# SMAC-2530.net
KiCad netlist of a schematic drawn in EAGLE
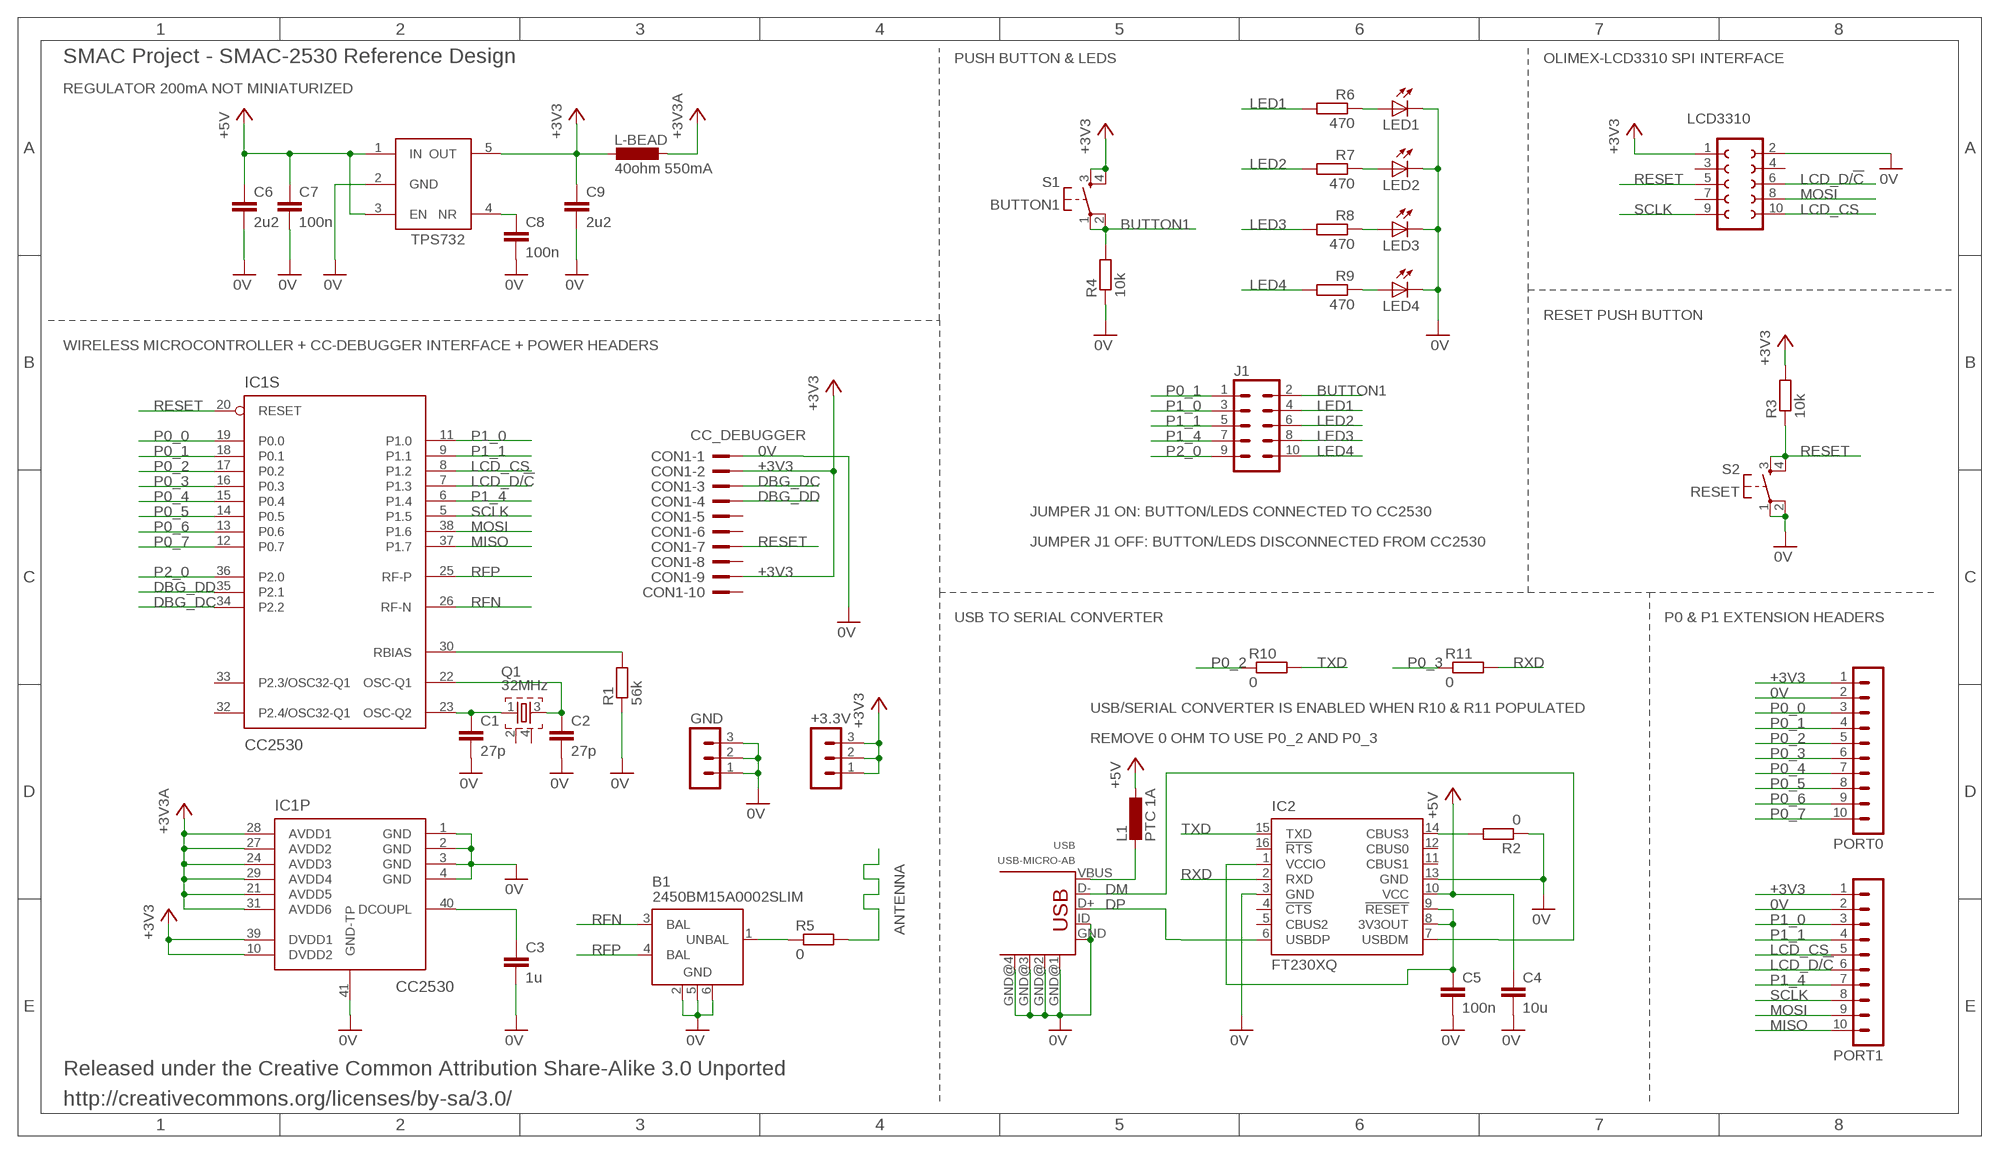
[diagram p0: schematic, sheet 1]

(export (version "E")
  (design (tool "Eeschema 10.0.6"))
  (components
    (comp (ref "+3.3V")
      (value "MA03-1")
      (footprint "eagle-import:MA03-1")
      (libsource (lib "eagle-import") (part "MA03-1"))
    )
    (comp (ref "B1")
      (value "2450BM15A0002SLIM")
      (footprint "eagle-import:2450BM15A0002-SLIM")
      (libsource (lib "eagle-import") (part "2450BM15A0002SLIM"))
    )
    (comp (ref "C1")
      (value "27p")
      (footprint "eagle-import:C0603K")
      (libsource (lib "eagle-import") (part "C-EUC0603K"))
    )
    (comp (ref "C2")
      (value "27p")
      (footprint "eagle-import:C0603K")
      (libsource (lib "eagle-import") (part "C-EUC0603K"))
    )
    (comp (ref "C3")
      (value "1u")
      (footprint "eagle-import:C0603K")
      (libsource (lib "eagle-import") (part "C-EUC0603K"))
    )
    (comp (ref "C4")
      (value "10u")
      (footprint "eagle-import:C0603K")
      (libsource (lib "eagle-import") (part "C-EUC0603K"))
    )
    (comp (ref "C5")
      (value "100n")
      (footprint "eagle-import:C0603K")
      (libsource (lib "eagle-import") (part "C-EUC0603K"))
    )
    (comp (ref "C6")
      (value "2u2")
      (footprint "eagle-import:C0603K")
      (libsource (lib "eagle-import") (part "C-EUC0603K"))
    )
    (comp (ref "C7")
      (value "100n")
      (footprint "eagle-import:C0603K")
      (libsource (lib "eagle-import") (part "C-EUC0603K"))
    )
    (comp (ref "C8")
      (value "100n")
      (footprint "eagle-import:C0603K")
      (libsource (lib "eagle-import") (part "C-EUC0603K"))
    )
    (comp (ref "C9")
      (value "2u2")
      (footprint "eagle-import:C0603K")
      (libsource (lib "eagle-import") (part "C-EUC0603K"))
    )
    (comp (ref "CON1")
      (value "CC_DEBUGGER")
      (footprint "eagle-import:PAK100_2500-10")
      (fields (field (name "MF") "3M") (field (name "MPN") "2510-6002UB"))
      (libsource (lib "eagle-import") (part "2510-"))
    )
    (comp (ref "GND")
      (value "MA03-1")
      (footprint "eagle-import:MA03-1")
      (libsource (lib "eagle-import") (part "MA03-1"))
    )
    (comp (ref "IC1")
      (value "CC2530")
      (footprint "eagle-import:QFN50P600X600X100-41N")
      (libsource (lib "eagle-import") (part "CC2530"))
    )
    (comp (ref "IC2")
      (value "FT230XQ")
      (footprint "eagle-import:QFN16")
      (libsource (lib "eagle-import") (part "FT230XQ"))
    )
    (comp (ref "IC3")
      (value "TPS732XX")
      (footprint "eagle-import:SOT23")
      (libsource (lib "eagle-import") (part "TPS732XX"))
    )
    (comp (ref "J1")
      (value "MA05-2")
      (footprint "eagle-import:MA05-2")
      (libsource (lib "eagle-import") (part "MA05-2"))
    )
    (comp (ref "L-BEAD")
      (value "40ohm 550mA")
      (footprint "eagle-import:L0603K")
      (libsource (lib "eagle-import") (part "L-EUL0603K"))
    )
    (comp (ref "L1")
      (value "PTC 1A")
      (footprint "eagle-import:L0603K")
      (libsource (lib "eagle-import") (part "L-EUL0603K"))
    )
    (comp (ref "LCD3310")
      (value "FE05-2")
      (footprint "eagle-import:FE05-2")
      (libsource (lib "eagle-import") (part "FE05-2"))
    )
    (comp (ref "LED1")
      (value "LEDCHIP-LED0805")
      (footprint "eagle-import:CHIP-LED0805")
      (libsource (lib "eagle-import") (part "LEDCHIP-LED0805"))
    )
    (comp (ref "LED2")
      (value "LEDCHIP-LED0805")
      (footprint "eagle-import:CHIP-LED0805")
      (libsource (lib "eagle-import") (part "LEDCHIP-LED0805"))
    )
    (comp (ref "LED3")
      (value "LEDCHIP-LED0805")
      (footprint "eagle-import:CHIP-LED0805")
      (libsource (lib "eagle-import") (part "LEDCHIP-LED0805"))
    )
    (comp (ref "LED4")
      (value "LEDCHIP-LED0805")
      (footprint "eagle-import:CHIP-LED0805")
      (libsource (lib "eagle-import") (part "LEDCHIP-LED0805"))
    )
    (comp (ref "PORT0")
      (value "MA10-1")
      (footprint "eagle-import:MA10-1")
      (libsource (lib "eagle-import") (part "MA10-1"))
    )
    (comp (ref "PORT1")
      (value "MA10-1")
      (footprint "eagle-import:MA10-1")
      (libsource (lib "eagle-import") (part "MA10-1"))
    )
    (comp (ref "Q1")
      (value "32MHz")
      (footprint "eagle-import:FA-128")
      (libsource (lib "eagle-import") (part "FA-128"))
    )
    (comp (ref "R1")
      (value "56k")
      (footprint "eagle-import:R0603K")
      (libsource (lib "eagle-import") (part "R-EU_R0603K"))
    )
    (comp (ref "R2")
      (value "0")
      (footprint "eagle-import:R0603K")
      (libsource (lib "eagle-import") (part "R-EU_R0603K"))
    )
    (comp (ref "R3")
      (value "10k")
      (footprint "eagle-import:R0603K")
      (libsource (lib "eagle-import") (part "R-EU_R0603K"))
    )
    (comp (ref "R4")
      (value "10k")
      (footprint "eagle-import:R0603K")
      (libsource (lib "eagle-import") (part "R-EU_R0603K"))
    )
    (comp (ref "R5")
      (value "0")
      (footprint "eagle-import:R0603K")
      (libsource (lib "eagle-import") (part "R-EU_R0603K"))
    )
    (comp (ref "R6")
      (value "470")
      (footprint "eagle-import:R0603K")
      (libsource (lib "eagle-import") (part "R-EU_R0603K"))
    )
    (comp (ref "R7")
      (value "470")
      (footprint "eagle-import:R0603K")
      (libsource (lib "eagle-import") (part "R-EU_R0603K"))
    )
    (comp (ref "R8")
      (value "470")
      (footprint "eagle-import:R0603K")
      (libsource (lib "eagle-import") (part "R-EU_R0603K"))
    )
    (comp (ref "R9")
      (value "470")
      (footprint "eagle-import:R0603K")
      (libsource (lib "eagle-import") (part "R-EU_R0603K"))
    )
    (comp (ref "R10")
      (value "0")
      (footprint "eagle-import:R0603K")
      (libsource (lib "eagle-import") (part "R-EU_R0603K"))
    )
    (comp (ref "R11")
      (value "0")
      (footprint "eagle-import:R0603K")
      (libsource (lib "eagle-import") (part "R-EU_R0603K"))
    )
    (comp (ref "S1")
      (value "BUTTON1")
      (footprint "eagle-import:ALCOSWITCH-SMD")
      (libsource (lib "eagle-import") (part "ALCOSWITCH-SMD"))
    )
    (comp (ref "S2")
      (value "RESET")
      (footprint "eagle-import:ALCOSWITCH-SMD")
      (libsource (lib "eagle-import") (part "ALCOSWITCH-SMD"))
    )
    (comp (ref "USB")
      (value "USB-MICRO-AB")
      (footprint "eagle-import:USB-UAB-S1")
      (libsource (lib "eagle-import") (part "USB-OTG_SHIELD"))
    )
  )
  (nets
    (net (code "1") (name "+3V3") (class "Default")
      (node (ref "+3.3V") (pin "1") (pinfunction "1_1") (pintype "passive"))
      (node (ref "+3.3V") (pin "2") (pinfunction "2_2") (pintype "passive"))
      (node (ref "+3.3V") (pin "3") (pinfunction "3_3") (pintype "passive"))
      (node (ref "C9") (pin "1") (pinfunction "1_1") (pintype "passive"))
      (node (ref "CON1") (pin "2") (pinfunction "KL_2") (pintype "passive"))
      (node (ref "CON1") (pin "9") (pinfunction "KL_9") (pintype "passive"))
      (node (ref "IC1") (pin "10") (pinfunction "DVDD2_10") (pintype "power_in"))
      (node (ref "IC1") (pin "39") (pinfunction "DVDD1_39") (pintype "power_in"))
      (node (ref "IC3") (pin "5") (pinfunction "OUT_5") (pintype "bidirectional"))
      (node (ref "L-BEAD") (pin "1") (pinfunction "1_1") (pintype "passive"))
      (node (ref "LCD3310") (pin "1") (pinfunction "1_1") (pintype "passive"))
      (node (ref "PORT0") (pin "1") (pinfunction "1_1") (pintype "passive"))
      (node (ref "PORT1") (pin "1") (pinfunction "1_1") (pintype "passive"))
      (node (ref "R3") (pin "2") (pinfunction "2_2") (pintype "passive"))
      (node (ref "S1") (pin "3") (pinfunction "S_3") (pintype "passive"))
      (node (ref "S1") (pin "4") (pinfunction "S1_4") (pintype "passive"))
    )
    (net (code "2") (name "+3V3A") (class "Default")
      (node (ref "IC1") (pin "21") (pinfunction "AVDD5_21") (pintype "power_in"))
      (node (ref "IC1") (pin "24") (pinfunction "AVDD3_24") (pintype "power_in"))
      (node (ref "IC1") (pin "27") (pinfunction "AVDD2_27") (pintype "power_in"))
      (node (ref "IC1") (pin "28") (pinfunction "AVDD1_28") (pintype "power_in"))
      (node (ref "IC1") (pin "29") (pinfunction "AVDD4_29") (pintype "power_in"))
      (node (ref "IC1") (pin "31") (pinfunction "AVDD6_31") (pintype "power_in"))
      (node (ref "L-BEAD") (pin "2") (pinfunction "2_2") (pintype "passive"))
    )
    (net (code "3") (name "+5V") (class "Default")
      (node (ref "C4") (pin "1") (pinfunction "1_1") (pintype "passive"))
      (node (ref "C6") (pin "1") (pinfunction "1_1") (pintype "passive"))
      (node (ref "C7") (pin "1") (pinfunction "1_1") (pintype "passive"))
      (node (ref "IC2") (pin "10") (pinfunction "VCC_10") (pintype "power_in"))
      (node (ref "IC3") (pin "1") (pinfunction "IN_1") (pintype "bidirectional"))
      (node (ref "IC3") (pin "3") (pinfunction "EN_3") (pintype "bidirectional"))
      (node (ref "L1") (pin "1") (pinfunction "1_1") (pintype "passive"))
    )
    (net (code "4") (name "/BUTTON1") (class "Default")
      (node (ref "J1") (pin "2") (pinfunction "2_2") (pintype "passive"))
      (node (ref "R4") (pin "2") (pinfunction "2_2") (pintype "passive"))
      (node (ref "S1") (pin "1") (pinfunction "P_1") (pintype "passive"))
      (node (ref "S1") (pin "2") (pinfunction "P1_2") (pintype "passive"))
    )
    (net (code "5") (name "/DBG_DC") (class "Default")
      (node (ref "CON1") (pin "3") (pinfunction "KL_3") (pintype "passive"))
      (node (ref "IC1") (pin "34") (pinfunction "P2.2_34") (pintype "bidirectional"))
    )
    (net (code "6") (name "/DBG_DD") (class "Default")
      (node (ref "CON1") (pin "4") (pinfunction "KL_4") (pintype "passive"))
      (node (ref "IC1") (pin "35") (pinfunction "P2.1_35") (pintype "bidirectional"))
    )
    (net (code "7") (name "/DM") (class "Default")
      (node (ref "IC2") (pin "7") (pinfunction "USBDM_7") (pintype "input"))
      (node (ref "USB") (pin "D-") (pinfunction "D-_D-") (pintype "bidirectional"))
    )
    (net (code "8") (name "/DP") (class "Default")
      (node (ref "IC2") (pin "6") (pinfunction "USBDP_6") (pintype "input"))
      (node (ref "USB") (pin "D+") (pinfunction "D+_D+") (pintype "bidirectional"))
    )
    (net (code "9") (name "/LCD_CS") (class "Default")
      (node (ref "IC1") (pin "8") (pinfunction "P1.2_8") (pintype "bidirectional"))
      (node (ref "LCD3310") (pin "10") (pinfunction "10_10") (pintype "passive"))
      (node (ref "PORT1") (pin "5") (pinfunction "5_5") (pintype "passive"))
    )
    (net (code "10") (name "/LCD_D{slash}~{C}") (class "Default")
      (node (ref "IC1") (pin "7") (pinfunction "P1.3_7") (pintype "bidirectional"))
      (node (ref "LCD3310") (pin "6") (pinfunction "6_6") (pintype "passive"))
      (node (ref "PORT1") (pin "6") (pinfunction "6_6") (pintype "passive"))
    )
    (net (code "11") (name "/LED1") (class "Default")
      (node (ref "J1") (pin "4") (pinfunction "4_4") (pintype "passive"))
      (node (ref "R6") (pin "2") (pinfunction "2_2") (pintype "passive"))
    )
    (net (code "12") (name "/LED2") (class "Default")
      (node (ref "J1") (pin "6") (pinfunction "6_6") (pintype "passive"))
      (node (ref "R7") (pin "2") (pinfunction "2_2") (pintype "passive"))
    )
    (net (code "13") (name "/LED3") (class "Default")
      (node (ref "J1") (pin "8") (pinfunction "8_8") (pintype "passive"))
      (node (ref "R8") (pin "2") (pinfunction "2_2") (pintype "passive"))
    )
    (net (code "14") (name "/LED4") (class "Default")
      (node (ref "J1") (pin "10") (pinfunction "10_10") (pintype "passive"))
      (node (ref "R9") (pin "2") (pinfunction "2_2") (pintype "passive"))
    )
    (net (code "15") (name "/MISO") (class "Default")
      (node (ref "IC1") (pin "37") (pinfunction "P1.7_37") (pintype "bidirectional"))
      (node (ref "PORT1") (pin "10") (pinfunction "10_10") (pintype "passive"))
    )
    (net (code "16") (name "/MOSI") (class "Default")
      (node (ref "IC1") (pin "38") (pinfunction "P1.6_38") (pintype "bidirectional"))
      (node (ref "LCD3310") (pin "8") (pinfunction "8_8") (pintype "passive"))
      (node (ref "PORT1") (pin "9") (pinfunction "9_9") (pintype "passive"))
    )
    (net (code "17") (name "/P0_0") (class "Default")
      (node (ref "IC1") (pin "19") (pinfunction "P0.0_19") (pintype "bidirectional"))
      (node (ref "PORT0") (pin "3") (pinfunction "3_3") (pintype "passive"))
    )
    (net (code "18") (name "/P0_1") (class "Default")
      (node (ref "IC1") (pin "18") (pinfunction "P0.1_18") (pintype "bidirectional"))
      (node (ref "J1") (pin "1") (pinfunction "1_1") (pintype "passive"))
      (node (ref "PORT0") (pin "4") (pinfunction "4_4") (pintype "passive"))
    )
    (net (code "19") (name "/P0_2") (class "Default")
      (node (ref "IC1") (pin "17") (pinfunction "P0.2_17") (pintype "bidirectional"))
      (node (ref "PORT0") (pin "5") (pinfunction "5_5") (pintype "passive"))
      (node (ref "R10") (pin "1") (pinfunction "1_1") (pintype "passive"))
    )
    (net (code "20") (name "/P0_3") (class "Default")
      (node (ref "IC1") (pin "16") (pinfunction "P0.3_16") (pintype "bidirectional"))
      (node (ref "PORT0") (pin "6") (pinfunction "6_6") (pintype "passive"))
      (node (ref "R11") (pin "1") (pinfunction "1_1") (pintype "passive"))
    )
    (net (code "21") (name "/P0_4") (class "Default")
      (node (ref "IC1") (pin "15") (pinfunction "P0.4_15") (pintype "bidirectional"))
      (node (ref "PORT0") (pin "7") (pinfunction "7_7") (pintype "passive"))
    )
    (net (code "22") (name "/P0_5") (class "Default")
      (node (ref "IC1") (pin "14") (pinfunction "P0.5_14") (pintype "bidirectional"))
      (node (ref "PORT0") (pin "8") (pinfunction "8_8") (pintype "passive"))
    )
    (net (code "23") (name "/P0_6") (class "Default")
      (node (ref "IC1") (pin "13") (pinfunction "P0.6_13") (pintype "bidirectional"))
      (node (ref "PORT0") (pin "9") (pinfunction "9_9") (pintype "passive"))
    )
    (net (code "24") (name "/P0_7") (class "Default")
      (node (ref "IC1") (pin "12") (pinfunction "P0.7_12") (pintype "bidirectional"))
      (node (ref "PORT0") (pin "10") (pinfunction "10_10") (pintype "passive"))
    )
    (net (code "25") (name "/P1_0") (class "Default")
      (node (ref "IC1") (pin "11") (pinfunction "P1.0_11") (pintype "bidirectional"))
      (node (ref "J1") (pin "3") (pinfunction "3_3") (pintype "passive"))
      (node (ref "PORT1") (pin "3") (pinfunction "3_3") (pintype "passive"))
    )
    (net (code "26") (name "/P1_1") (class "Default")
      (node (ref "IC1") (pin "9") (pinfunction "P1.1_9") (pintype "bidirectional"))
      (node (ref "J1") (pin "5") (pinfunction "5_5") (pintype "passive"))
      (node (ref "PORT1") (pin "4") (pinfunction "4_4") (pintype "passive"))
    )
    (net (code "27") (name "/P1_4") (class "Default")
      (node (ref "IC1") (pin "6") (pinfunction "P1.4_6") (pintype "bidirectional"))
      (node (ref "J1") (pin "7") (pinfunction "7_7") (pintype "passive"))
      (node (ref "PORT1") (pin "7") (pinfunction "7_7") (pintype "passive"))
    )
    (net (code "28") (name "/P2_0") (class "Default")
      (node (ref "IC1") (pin "36") (pinfunction "P2.0_36") (pintype "bidirectional"))
      (node (ref "J1") (pin "9") (pinfunction "9_9") (pintype "passive"))
    )
    (net (code "29") (name "/RESET") (class "Default")
      (node (ref "CON1") (pin "7") (pinfunction "KL_7") (pintype "passive"))
      (node (ref "IC1") (pin "20") (pinfunction "RESET_20") (pintype "input"))
      (node (ref "LCD3310") (pin "5") (pinfunction "5_5") (pintype "passive"))
      (node (ref "R3") (pin "1") (pinfunction "1_1") (pintype "passive"))
      (node (ref "S2") (pin "3") (pinfunction "S_3") (pintype "passive"))
      (node (ref "S2") (pin "4") (pinfunction "S1_4") (pintype "passive"))
    )
    (net (code "30") (name "/RFN") (class "Default")
      (node (ref "B1") (pin "3") (pinfunction "BAL_3") (pintype "passive"))
      (node (ref "IC1") (pin "26") (pinfunction "RF-N_26") (pintype "bidirectional"))
    )
    (net (code "31") (name "/RFP") (class "Default")
      (node (ref "B1") (pin "4") (pinfunction "BAL_4") (pintype "passive"))
      (node (ref "IC1") (pin "25") (pinfunction "RF-P_25") (pintype "bidirectional"))
    )
    (net (code "32") (name "/RXD") (class "Default")
      (node (ref "IC2") (pin "2") (pinfunction "RXD_2") (pintype "input"))
      (node (ref "R11") (pin "2") (pinfunction "2_2") (pintype "passive"))
    )
    (net (code "33") (name "/SCLK") (class "Default")
      (node (ref "IC1") (pin "5") (pinfunction "P1.5_5") (pintype "bidirectional"))
      (node (ref "LCD3310") (pin "9") (pinfunction "9_9") (pintype "passive"))
      (node (ref "PORT1") (pin "8") (pinfunction "8_8") (pintype "passive"))
    )
    (net (code "34") (name "/TXD") (class "Default")
      (node (ref "IC2") (pin "15") (pinfunction "TXD_15") (pintype "output"))
      (node (ref "R10") (pin "2") (pinfunction "2_2") (pintype "passive"))
    )
    (net (code "35") (name "0V") (class "Default")
      (node (ref "B1") (pin "2") (pinfunction "GND_2") (pintype "passive"))
      (node (ref "B1") (pin "5") (pinfunction "GND_5") (pintype "passive"))
      (node (ref "B1") (pin "6") (pinfunction "GND_6") (pintype "passive"))
      (node (ref "C1") (pin "2") (pinfunction "2_2") (pintype "passive"))
      (node (ref "C2") (pin "2") (pinfunction "2_2") (pintype "passive"))
      (node (ref "C3") (pin "2") (pinfunction "2_2") (pintype "passive"))
      (node (ref "C4") (pin "2") (pinfunction "2_2") (pintype "passive"))
      (node (ref "C5") (pin "2") (pinfunction "2_2") (pintype "passive"))
      (node (ref "C6") (pin "2") (pinfunction "2_2") (pintype "passive"))
      (node (ref "C7") (pin "2") (pinfunction "2_2") (pintype "passive"))
      (node (ref "C8") (pin "2") (pinfunction "2_2") (pintype "passive"))
      (node (ref "C9") (pin "2") (pinfunction "2_2") (pintype "passive"))
      (node (ref "CON1") (pin "1") (pinfunction "KL_1") (pintype "passive"))
      (node (ref "GND") (pin "1") (pinfunction "1_1") (pintype "passive"))
      (node (ref "GND") (pin "2") (pinfunction "2_2") (pintype "passive"))
      (node (ref "GND") (pin "3") (pinfunction "3_3") (pintype "passive"))
      (node (ref "IC1") (pin "1") (pinfunction "GND_1") (pintype "power_in"))
      (node (ref "IC1") (pin "2") (pinfunction "GND_2") (pintype "power_in"))
      (node (ref "IC1") (pin "3") (pinfunction "GND_3") (pintype "power_in"))
      (node (ref "IC1") (pin "4") (pinfunction "GND_4") (pintype "power_in"))
      (node (ref "IC1") (pin "41") (pinfunction "GND-TP_41") (pintype "power_in"))
      (node (ref "IC2") (pin "13") (pinfunction "GND_13") (pintype "power_in"))
      (node (ref "IC2") (pin "3") (pinfunction "GND_3") (pintype "power_in"))
      (node (ref "IC3") (pin "2") (pinfunction "GND_2") (pintype "bidirectional"))
      (node (ref "LCD3310") (pin "2") (pinfunction "2_2") (pintype "passive"))
      (node (ref "LED1") (pin "C") (pinfunction "C_C") (pintype "passive"))
      (node (ref "LED2") (pin "C") (pinfunction "C_C") (pintype "passive"))
      (node (ref "LED3") (pin "C") (pinfunction "C_C") (pintype "passive"))
      (node (ref "LED4") (pin "C") (pinfunction "C_C") (pintype "passive"))
      (node (ref "PORT0") (pin "2") (pinfunction "2_2") (pintype "passive"))
      (node (ref "PORT1") (pin "2") (pinfunction "2_2") (pintype "passive"))
      (node (ref "R1") (pin "1") (pinfunction "1_1") (pintype "passive"))
      (node (ref "R2") (pin "1") (pinfunction "1_1") (pintype "passive"))
      (node (ref "R4") (pin "1") (pinfunction "1_1") (pintype "passive"))
      (node (ref "R5") (pin "2") (pinfunction "2_2") (pintype "passive"))
      (node (ref "S2") (pin "1") (pinfunction "P_1") (pintype "passive"))
      (node (ref "S2") (pin "2") (pinfunction "P1_2") (pintype "passive"))
      (node (ref "USB") (pin "GND") (pinfunction "GND_GND") (pintype "power_in"))
      (node (ref "USB") (pin "GND@1") (pinfunction "GND_GND@1") (pintype "power_in"))
      (node (ref "USB") (pin "GND@2") (pinfunction "GND_GND@2") (pintype "power_in"))
      (node (ref "USB") (pin "GND@3") (pinfunction "GND_GND@3") (pintype "power_in"))
      (node (ref "USB") (pin "GND@4") (pinfunction "GND_GND@4") (pintype "power_in"))
      (node (ref "USB") (pin "ID") (pinfunction "ID_ID") (pintype "bidirectional"))
    )
    (net (code "36") (name "Net-(B1-UNBAL)") (class "Default")
      (node (ref "B1") (pin "1") (pinfunction "UNBAL_1") (pintype "passive"))
      (node (ref "R5") (pin "1") (pinfunction "1_1") (pintype "passive"))
    )
    (net (code "37") (name "Net-(IC1A-DCOUPL)") (class "Default")
      (node (ref "C3") (pin "1") (pinfunction "1_1") (pintype "passive"))
      (node (ref "IC1") (pin "40") (pinfunction "DCOUPL_40") (pintype "power_in"))
    )
    (net (code "38") (name "Net-(IC1B-OSC-Q1)") (class "Default")
      (node (ref "C2") (pin "1") (pinfunction "1_1") (pintype "passive"))
      (node (ref "IC1") (pin "22") (pinfunction "OSC-Q1_22") (pintype "bidirectional"))
      (node (ref "Q1") (pin "3") (pinfunction "3_3") (pintype "passive"))
    )
    (net (code "39") (name "Net-(IC1B-OSC-Q2)") (class "Default")
      (node (ref "C1") (pin "1") (pinfunction "1_1") (pintype "passive"))
      (node (ref "IC1") (pin "23") (pinfunction "OSC-Q2_23") (pintype "bidirectional"))
      (node (ref "Q1") (pin "1") (pinfunction "1_1") (pintype "passive"))
    )
    (net (code "40") (name "Net-(IC1B-RBIAS)") (class "Default")
      (node (ref "IC1") (pin "30") (pinfunction "RBIAS_30") (pintype "bidirectional"))
      (node (ref "R1") (pin "2") (pinfunction "2_2") (pintype "passive"))
    )
    (net (code "41") (name "Net-(IC2-3V3OUT)") (class "Default")
      (node (ref "C5") (pin "1") (pinfunction "1_1") (pintype "passive"))
      (node (ref "IC2") (pin "1") (pinfunction "VCCIO_1") (pintype "power_in"))
      (node (ref "IC2") (pin "8") (pinfunction "3V3OUT_8") (pintype "output"))
      (node (ref "IC2") (pin "9") (pinfunction "~{RESET}_9") (pintype "input"))
    )
    (net (code "42") (name "Net-(IC2-CBUS3)") (class "Default")
      (node (ref "IC2") (pin "14") (pinfunction "CBUS3_14") (pintype "bidirectional"))
      (node (ref "R2") (pin "2") (pinfunction "2_2") (pintype "passive"))
    )
    (net (code "43") (name "Net-(IC3-NR)") (class "Default")
      (node (ref "C8") (pin "1") (pinfunction "1_1") (pintype "passive"))
      (node (ref "IC3") (pin "4") (pinfunction "NR_4") (pintype "bidirectional"))
    )
    (net (code "44") (name "Net-(L1-Pad2)") (class "Default")
      (node (ref "L1") (pin "2") (pinfunction "2_2") (pintype "passive"))
      (node (ref "USB") (pin "VBUS") (pinfunction "VBUS_VBUS") (pintype "power_in"))
    )
    (net (code "45") (name "Net-(LED1-PadA)") (class "Default")
      (node (ref "LED1") (pin "A") (pinfunction "A_A") (pintype "passive"))
      (node (ref "R6") (pin "1") (pinfunction "1_1") (pintype "passive"))
    )
    (net (code "46") (name "Net-(LED2-PadA)") (class "Default")
      (node (ref "LED2") (pin "A") (pinfunction "A_A") (pintype "passive"))
      (node (ref "R7") (pin "1") (pinfunction "1_1") (pintype "passive"))
    )
    (net (code "47") (name "Net-(LED3-PadA)") (class "Default")
      (node (ref "LED3") (pin "A") (pinfunction "A_A") (pintype "passive"))
      (node (ref "R8") (pin "1") (pinfunction "1_1") (pintype "passive"))
    )
    (net (code "48") (name "Net-(LED4-PadA)") (class "Default")
      (node (ref "LED4") (pin "A") (pinfunction "A_A") (pintype "passive"))
      (node (ref "R9") (pin "1") (pinfunction "1_1") (pintype "passive"))
    )
    (net (code "49") (name "unconnected-(CON1B-KL-Pad10)") (class "Default")
      (node (ref "CON1") (pin "10") (pinfunction "KL_10") (pintype "passive"))
    )
    (net (code "50") (name "unconnected-(CON1F-KL-Pad5)") (class "Default")
      (node (ref "CON1") (pin "5") (pinfunction "KL_5") (pintype "passive"))
    )
    (net (code "51") (name "unconnected-(CON1G-KL-Pad6)") (class "Default")
      (node (ref "CON1") (pin "6") (pinfunction "KL_6") (pintype "passive"))
    )
    (net (code "52") (name "unconnected-(CON1I-KL-Pad8)") (class "Default")
      (node (ref "CON1") (pin "8") (pinfunction "KL_8") (pintype "passive"))
    )
    (net (code "53") (name "unconnected-(IC1B-P2.3{slash}OSC32-Q1-Pad33)") (class "Default")
      (node (ref "IC1") (pin "33") (pinfunction "P2.3/OSC32-Q1_33") (pintype "bidirectional"))
    )
    (net (code "54") (name "unconnected-(IC1B-P2.4{slash}OSC32-Q1-Pad32)") (class "Default")
      (node (ref "IC1") (pin "32") (pinfunction "P2.4/OSC32-Q1_32") (pintype "bidirectional"))
    )
    (net (code "55") (name "unconnected-(IC2-CBUS0-Pad12)") (class "Default")
      (node (ref "IC2") (pin "12") (pinfunction "CBUS0_12") (pintype "bidirectional"))
    )
    (net (code "56") (name "unconnected-(IC2-CBUS1-Pad11)") (class "Default")
      (node (ref "IC2") (pin "11") (pinfunction "CBUS1_11") (pintype "bidirectional"))
    )
    (net (code "57") (name "unconnected-(IC2-CBUS2-Pad5)") (class "Default")
      (node (ref "IC2") (pin "5") (pinfunction "CBUS2_5") (pintype "bidirectional"))
    )
    (net (code "58") (name "unconnected-(IC2-~{CTS}-Pad4)") (class "Default")
      (node (ref "IC2") (pin "4") (pinfunction "~{CTS}_4") (pintype "input"))
    )
    (net (code "59") (name "unconnected-(IC2-~{RTS}-Pad16)") (class "Default")
      (node (ref "IC2") (pin "16") (pinfunction "~{RTS}_16") (pintype "output"))
    )
    (net (code "60") (name "unconnected-(LCD3310-Pad3)") (class "Default")
      (node (ref "LCD3310") (pin "3") (pinfunction "3_3") (pintype "passive"))
    )
    (net (code "61") (name "unconnected-(LCD3310-Pad4)") (class "Default")
      (node (ref "LCD3310") (pin "4") (pinfunction "4_4") (pintype "passive"))
    )
    (net (code "62") (name "unconnected-(LCD3310-Pad7)") (class "Default")
      (node (ref "LCD3310") (pin "7") (pinfunction "7_7") (pintype "passive"))
    )
    (net (code "63") (name "unconnected-(Q1-Pad2)") (class "Default")
      (node (ref "Q1") (pin "2") (pinfunction "2_2") (pintype "passive"))
    )
    (net (code "64") (name "unconnected-(Q1-Pad4)") (class "Default")
      (node (ref "Q1") (pin "4") (pinfunction "4_4") (pintype "passive"))
    )
  )
)
